# bbf-supply.net
KiCad netlist of a schematic drawn in EAGLE
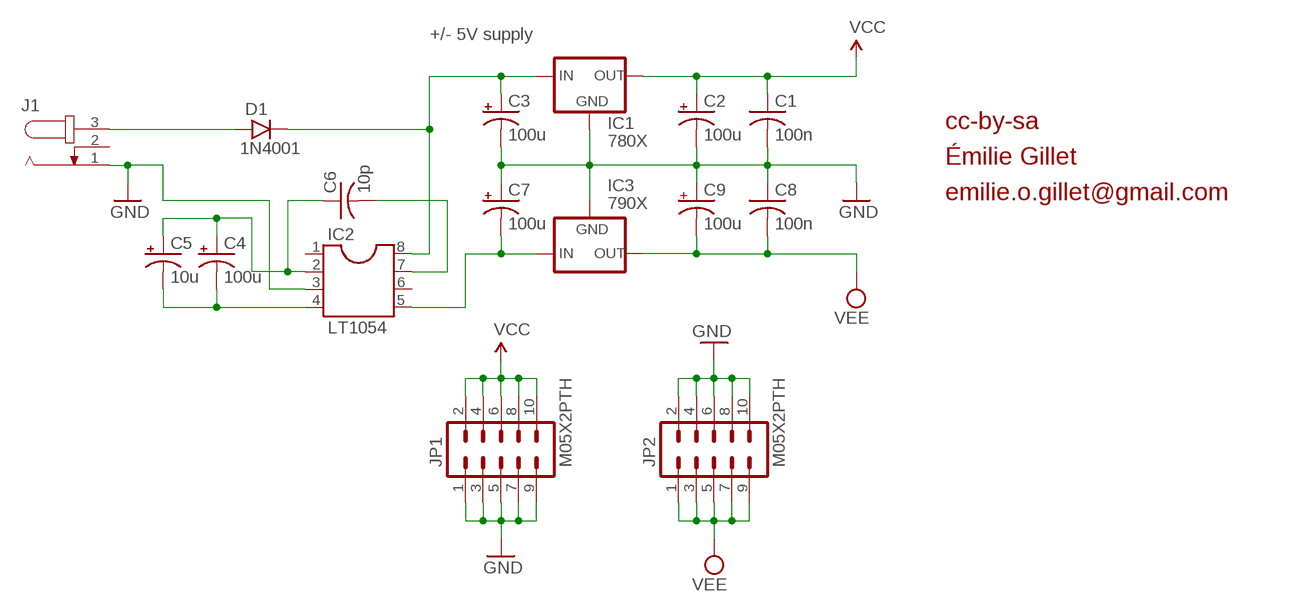
[diagram p0: schematic, sheet 1]

(export (version "E")
  (design (tool "Eeschema 10.0.6"))
  (components
    (comp (ref "C1")
      (value "100n")
      (footprint "eagle-import:C025-025X050")
      (libsource (lib "eagle-import") (part "C-US025-025X050"))
    )
    (comp (ref "C2")
      (value "100u")
      (footprint "eagle-import:E2,5-7")
      (libsource (lib "eagle-import") (part "CPOL-USE2.5-7"))
    )
    (comp (ref "C3")
      (value "100u")
      (footprint "eagle-import:E2,5-7")
      (libsource (lib "eagle-import") (part "CPOL-USE2.5-7"))
    )
    (comp (ref "C4")
      (value "100u")
      (footprint "eagle-import:E2,5-6")
      (libsource (lib "eagle-import") (part "CPOL-USE2.5-6"))
    )
    (comp (ref "C5")
      (value "10u")
      (footprint "eagle-import:E2,5-5")
      (libsource (lib "eagle-import") (part "CPOL-USE2.5-5"))
    )
    (comp (ref "C6")
      (value "10p")
      (footprint "eagle-import:C025-025X050")
      (libsource (lib "eagle-import") (part "C-US025-025X050"))
    )
    (comp (ref "C7")
      (value "100u")
      (footprint "eagle-import:E2,5-7")
      (libsource (lib "eagle-import") (part "CPOL-USE2.5-7"))
    )
    (comp (ref "C8")
      (value "100n")
      (footprint "eagle-import:C025-025X050")
      (libsource (lib "eagle-import") (part "C-US025-025X050"))
    )
    (comp (ref "C9")
      (value "100u")
      (footprint "eagle-import:E2,5-7")
      (libsource (lib "eagle-import") (part "CPOL-USE2.5-7"))
    )
    (comp (ref "D1")
      (value "1N4001")
      (footprint "eagle-import:DO41-3")
      (libsource (lib "eagle-import") (part "1N400X.3"))
    )
    (comp (ref "IC1")
      (value "780X")
      (footprint "eagle-import:78XXS")
      (libsource (lib "eagle-import") (part "78XXS"))
    )
    (comp (ref "IC2")
      (value "LT1054")
      (footprint "eagle-import:DIL08")
      (libsource (lib "eagle-import") (part "DIL8"))
    )
    (comp (ref "IC3")
      (value "790X")
      (footprint "eagle-import:79XXS")
      (libsource (lib "eagle-import") (part "79XXS"))
    )
    (comp (ref "J1")
      (value "JACK-PLUG2")
      (footprint "eagle-import:SPC4078_BIG_HOLES")
      (libsource (lib "eagle-import") (part "JACK-PLUG2"))
    )
    (comp (ref "JP1")
      (value "M05X2PTH")
      (footprint "eagle-import:AVR_ICSP")
      (libsource (lib "eagle-import") (part "M05X2PTH"))
    )
    (comp (ref "JP2")
      (value "M05X2PTH")
      (footprint "eagle-import:AVR_ICSP")
      (libsource (lib "eagle-import") (part "M05X2PTH"))
    )
  )
  (nets
    (net (code "1") (name "GND") (class "Default")
      (node (ref "C1") (pin "2") (pinfunction "2_2") (pintype "passive"))
      (node (ref "C2") (pin "-") (pinfunction "-_-") (pintype "passive"))
      (node (ref "C3") (pin "-") (pinfunction "-_-") (pintype "passive"))
      (node (ref "C7") (pin "+") (pinfunction "+_+") (pintype "passive"))
      (node (ref "C8") (pin "1") (pinfunction "1_1") (pintype "passive"))
      (node (ref "C9") (pin "+") (pinfunction "+_+") (pintype "passive"))
      (node (ref "IC1") (pin "GND") (pinfunction "GND_GND") (pintype "input"))
      (node (ref "IC2") (pin "3") (pinfunction "3_3") (pintype "passive"))
      (node (ref "IC3") (pin "GND") (pinfunction "GND_GND") (pintype "input"))
      (node (ref "J1") (pin "1") (pinfunction "1_1") (pintype "passive"))
      (node (ref "JP1") (pin "1") (pinfunction "1_1") (pintype "passive"))
      (node (ref "JP1") (pin "3") (pinfunction "3_3") (pintype "passive"))
      (node (ref "JP1") (pin "5") (pinfunction "5_5") (pintype "passive"))
      (node (ref "JP1") (pin "7") (pinfunction "7_7") (pintype "passive"))
      (node (ref "JP1") (pin "9") (pinfunction "9_9") (pintype "passive"))
      (node (ref "JP2") (pin "10") (pinfunction "10_10") (pintype "passive"))
      (node (ref "JP2") (pin "2") (pinfunction "2_2") (pintype "passive"))
      (node (ref "JP2") (pin "4") (pinfunction "4_4") (pintype "passive"))
      (node (ref "JP2") (pin "6") (pinfunction "6_6") (pintype "passive"))
      (node (ref "JP2") (pin "8") (pinfunction "8_8") (pintype "passive"))
    )
    (net (code "2") (name "Net-(C3-Pad+)") (class "Default")
      (node (ref "C3") (pin "+") (pinfunction "+_+") (pintype "passive"))
      (node (ref "D1") (pin "C") (pinfunction "C_C") (pintype "passive"))
      (node (ref "IC1") (pin "IN") (pinfunction "IN_IN") (pintype "input"))
      (node (ref "IC2") (pin "8") (pinfunction "8_8") (pintype "passive"))
    )
    (net (code "3") (name "Net-(C4-Pad+)") (class "Default")
      (node (ref "C4") (pin "+") (pinfunction "+_+") (pintype "passive"))
      (node (ref "C5") (pin "+") (pinfunction "+_+") (pintype "passive"))
      (node (ref "C6") (pin "1") (pinfunction "1_1") (pintype "passive"))
      (node (ref "IC2") (pin "2") (pinfunction "2_2") (pintype "passive"))
    )
    (net (code "4") (name "Net-(C4-Pad-)") (class "Default")
      (node (ref "C4") (pin "-") (pinfunction "-_-") (pintype "passive"))
      (node (ref "C5") (pin "-") (pinfunction "-_-") (pintype "passive"))
      (node (ref "IC2") (pin "4") (pinfunction "4_4") (pintype "passive"))
    )
    (net (code "5") (name "Net-(C6-Pad2)") (class "Default")
      (node (ref "C6") (pin "2") (pinfunction "2_2") (pintype "passive"))
      (node (ref "IC2") (pin "7") (pinfunction "7_7") (pintype "passive"))
    )
    (net (code "6") (name "Net-(C7-Pad-)") (class "Default")
      (node (ref "C7") (pin "-") (pinfunction "-_-") (pintype "passive"))
      (node (ref "IC2") (pin "5") (pinfunction "5_5") (pintype "passive"))
      (node (ref "IC3") (pin "IN") (pinfunction "IN_IN") (pintype "input"))
    )
    (net (code "7") (name "Net-(D1-PadA)") (class "Default")
      (node (ref "D1") (pin "A") (pinfunction "A_A") (pintype "passive"))
      (node (ref "J1") (pin "3") (pinfunction "3_3") (pintype "passive"))
    )
    (net (code "8") (name "VCC") (class "Default")
      (node (ref "C1") (pin "1") (pinfunction "1_1") (pintype "passive"))
      (node (ref "C2") (pin "+") (pinfunction "+_+") (pintype "passive"))
      (node (ref "IC1") (pin "OUT") (pinfunction "OUT_OUT") (pintype "passive"))
      (node (ref "JP1") (pin "10") (pinfunction "10_10") (pintype "passive"))
      (node (ref "JP1") (pin "2") (pinfunction "2_2") (pintype "passive"))
      (node (ref "JP1") (pin "4") (pinfunction "4_4") (pintype "passive"))
      (node (ref "JP1") (pin "6") (pinfunction "6_6") (pintype "passive"))
      (node (ref "JP1") (pin "8") (pinfunction "8_8") (pintype "passive"))
    )
    (net (code "9") (name "VEE") (class "Default")
      (node (ref "C8") (pin "2") (pinfunction "2_2") (pintype "passive"))
      (node (ref "C9") (pin "-") (pinfunction "-_-") (pintype "passive"))
      (node (ref "IC3") (pin "OUT") (pinfunction "OUT_OUT") (pintype "passive"))
      (node (ref "JP2") (pin "1") (pinfunction "1_1") (pintype "passive"))
      (node (ref "JP2") (pin "3") (pinfunction "3_3") (pintype "passive"))
      (node (ref "JP2") (pin "5") (pinfunction "5_5") (pintype "passive"))
      (node (ref "JP2") (pin "7") (pinfunction "7_7") (pintype "passive"))
      (node (ref "JP2") (pin "9") (pinfunction "9_9") (pintype "passive"))
    )
    (net (code "10") (name "unconnected-(IC2-Pad1)") (class "Default")
      (node (ref "IC2") (pin "1") (pinfunction "1_1") (pintype "passive"))
    )
    (net (code "11") (name "unconnected-(IC2-Pad6)") (class "Default")
      (node (ref "IC2") (pin "6") (pinfunction "6_6") (pintype "passive"))
    )
    (net (code "12") (name "unconnected-(J1-Pad2)") (class "Default")
      (node (ref "J1") (pin "2") (pinfunction "2_2") (pintype "passive"))
    )
  )
)
